# QuadOpAmp.net
KiCad netlist of a schematic drawn in EAGLE
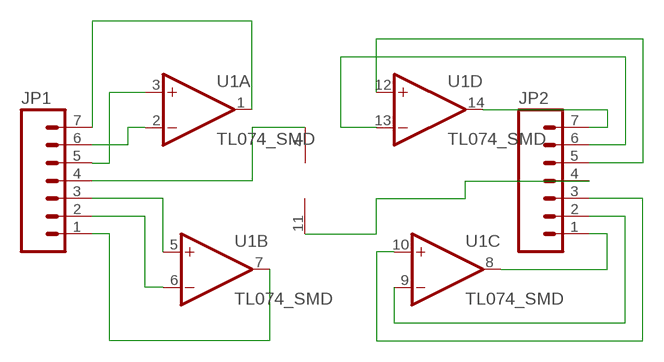
[diagram p0: schematic, sheet 1]

(export (version "E")
  (design (tool "Eeschema 10.0.6"))
  (components
    (comp (ref "JP1")
      (value "M07LOCK")
      (footprint "eagle-import:1X07_LOCK")
      (libsource (lib "eagle-import") (part "M07LOCK"))
    )
    (comp (ref "JP2")
      (value "M07LOCK")
      (footprint "eagle-import:1X07_LOCK")
      (libsource (lib "eagle-import") (part "M07LOCK"))
    )
    (comp (ref "U1")
      (value "TL074_SMD")
      (footprint "eagle-import:SO14")
      (libsource (lib "eagle-import") (part "TL074_SMD"))
    )
  )
  (nets
    (net (code "1") (name "Net-(U1A-+IN)") (class "Default")
      (node (ref "JP1") (pin "5") (pinfunction "5_5") (pintype "passive"))
      (node (ref "U1") (pin "3") (pinfunction "+IN_3") (pintype "input"))
    )
    (net (code "2") (name "Net-(U1A--IN)") (class "Default")
      (node (ref "JP1") (pin "6") (pinfunction "6_6") (pintype "passive"))
      (node (ref "U1") (pin "2") (pinfunction "-IN_2") (pintype "input"))
    )
    (net (code "3") (name "Net-(U1A-OUT)") (class "Default")
      (node (ref "JP1") (pin "7") (pinfunction "7_7") (pintype "passive"))
      (node (ref "U1") (pin "1") (pinfunction "OUT_1") (pintype "output"))
    )
    (net (code "4") (name "Net-(U1B-+IN)") (class "Default")
      (node (ref "JP1") (pin "3") (pinfunction "3_3") (pintype "passive"))
      (node (ref "U1") (pin "5") (pinfunction "+IN_5") (pintype "input"))
    )
    (net (code "5") (name "Net-(U1B--IN)") (class "Default")
      (node (ref "JP1") (pin "2") (pinfunction "2_2") (pintype "passive"))
      (node (ref "U1") (pin "6") (pinfunction "-IN_6") (pintype "input"))
    )
    (net (code "6") (name "Net-(U1B-OUT)") (class "Default")
      (node (ref "JP1") (pin "1") (pinfunction "1_1") (pintype "passive"))
      (node (ref "U1") (pin "7") (pinfunction "OUT_7") (pintype "output"))
    )
    (net (code "7") (name "Net-(U1C-+IN)") (class "Default")
      (node (ref "JP2") (pin "3") (pinfunction "3_3") (pintype "passive"))
      (node (ref "U1") (pin "10") (pinfunction "+IN_10") (pintype "input"))
    )
    (net (code "8") (name "Net-(U1C--IN)") (class "Default")
      (node (ref "JP2") (pin "2") (pinfunction "2_2") (pintype "passive"))
      (node (ref "U1") (pin "9") (pinfunction "-IN_9") (pintype "input"))
    )
    (net (code "9") (name "Net-(U1C-OUT)") (class "Default")
      (node (ref "JP2") (pin "1") (pinfunction "1_1") (pintype "passive"))
      (node (ref "U1") (pin "8") (pinfunction "OUT_8") (pintype "output"))
    )
    (net (code "10") (name "Net-(U1D-+IN)") (class "Default")
      (node (ref "JP2") (pin "5") (pinfunction "5_5") (pintype "passive"))
      (node (ref "U1") (pin "12") (pinfunction "+IN_12") (pintype "input"))
    )
    (net (code "11") (name "Net-(U1D--IN)") (class "Default")
      (node (ref "JP2") (pin "6") (pinfunction "6_6") (pintype "passive"))
      (node (ref "U1") (pin "13") (pinfunction "-IN_13") (pintype "input"))
    )
    (net (code "12") (name "Net-(U1D-OUT)") (class "Default")
      (node (ref "JP2") (pin "7") (pinfunction "7_7") (pintype "passive"))
      (node (ref "U1") (pin "14") (pinfunction "OUT_14") (pintype "output"))
    )
    (net (code "13") (name "Net-(U1E-V+)") (class "Default")
      (node (ref "JP1") (pin "4") (pinfunction "4_4") (pintype "passive"))
      (node (ref "U1") (pin "4") (pinfunction "V+_4") (pintype "power_in"))
    )
    (net (code "14") (name "Net-(U1E-V-)") (class "Default")
      (node (ref "JP2") (pin "4") (pinfunction "4_4") (pintype "passive"))
      (node (ref "U1") (pin "11") (pinfunction "V-_11") (pintype "power_in"))
    )
  )
)
